# OttoPi10-RPi3A-HAT.net
KiCad netlist of a schematic drawn in EAGLE
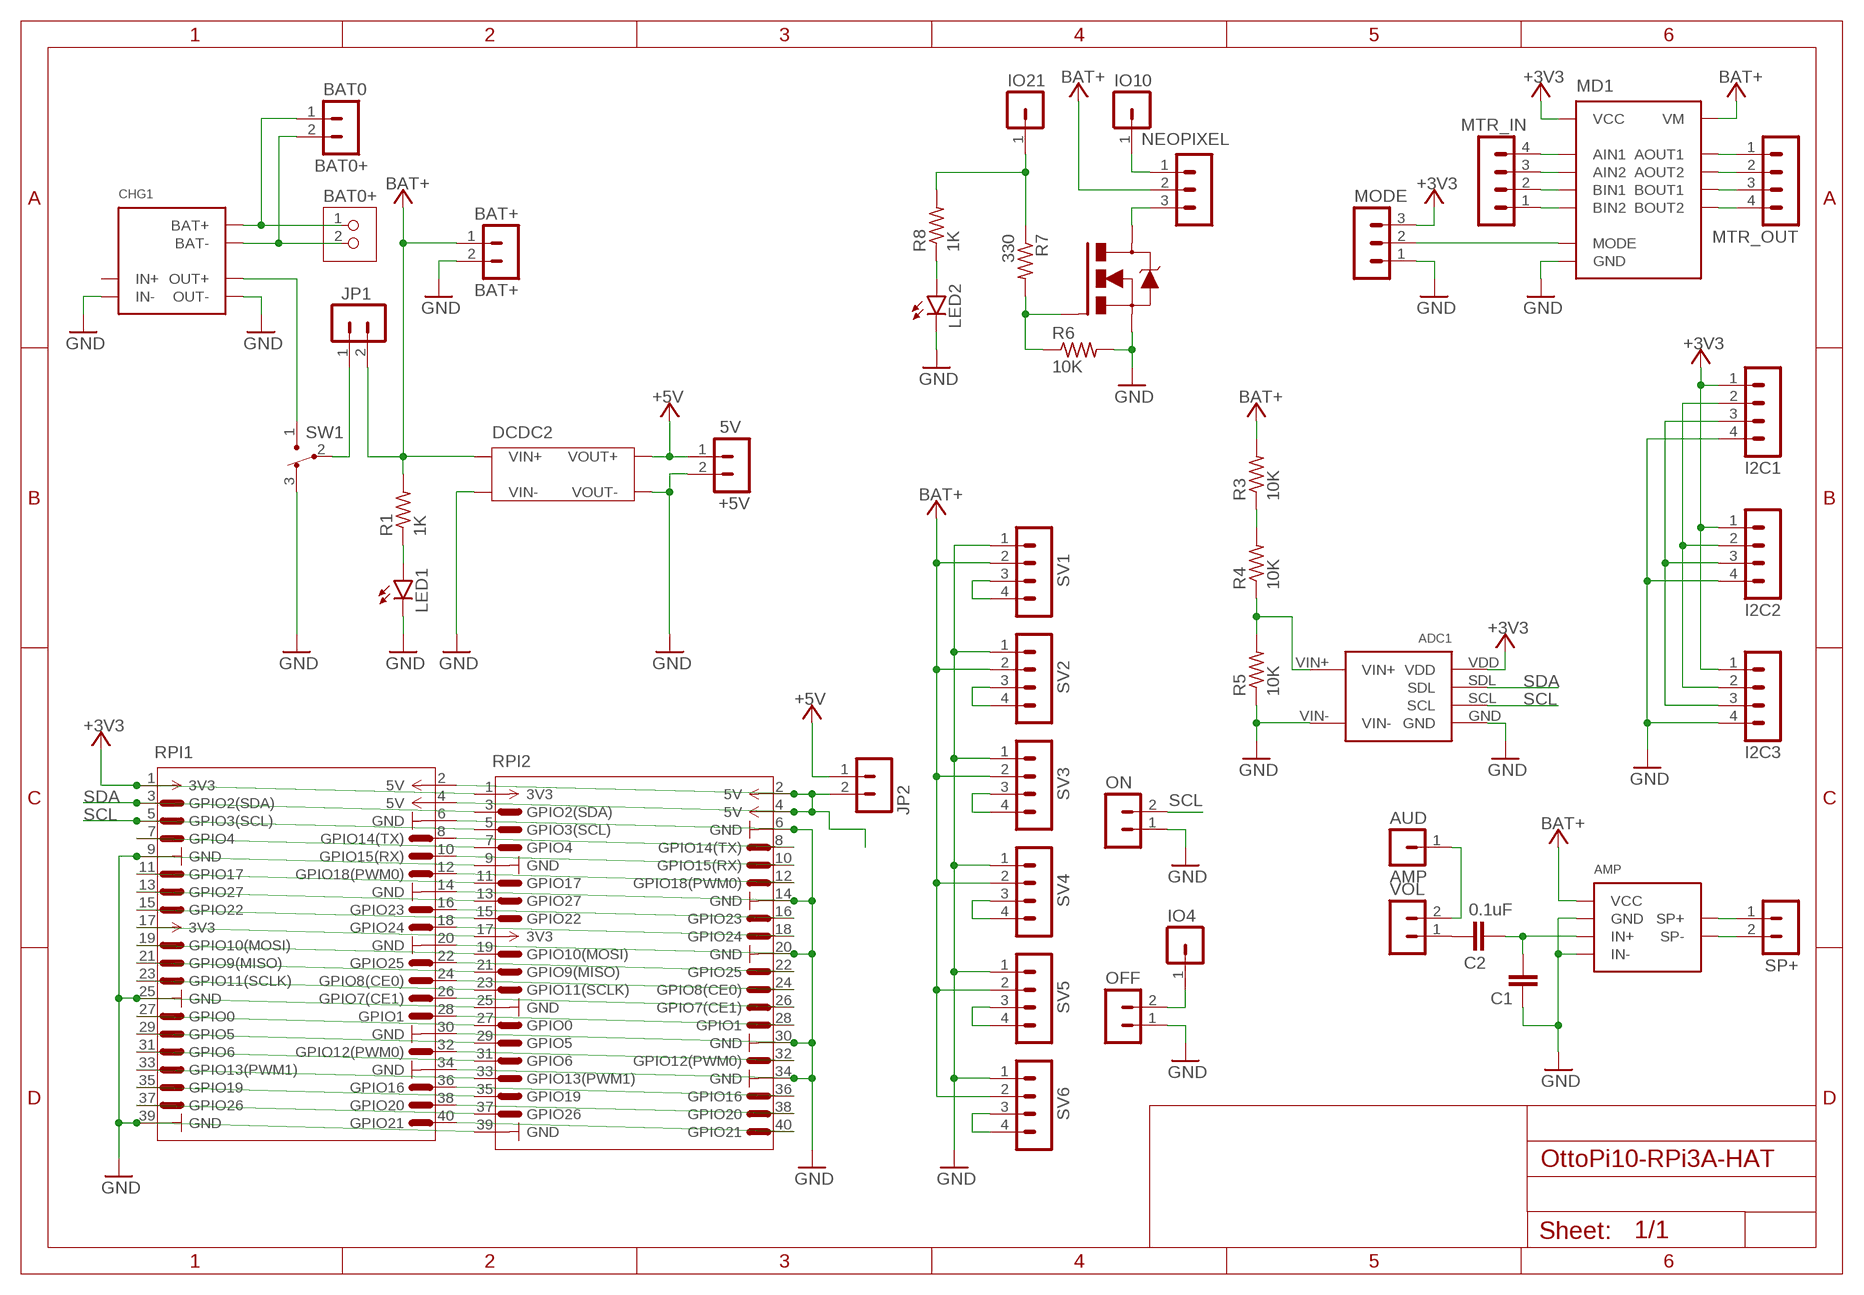
[diagram p0: schematic, sheet 1]

(export (version "E")
  (design (tool "Eeschema 10.0.6"))
  (components
    (comp (ref "+5V")
      (value "5V")
      (footprint "eagle-import:PINHEAD-MA02-1")
      (libsource (lib "eagle-import") (part "PINHEAD-MA02-1"))
    )
    (comp (ref "ADC1")
      (value "MCP3425MOD")
      (footprint "eagle-import:MCP3425MOD")
      (libsource (lib "eagle-import") (part "MCP3425MOD"))
    )
    (comp (ref "AMP")
      (value "AMP")
      (footprint "eagle-import:PAM8012MOD-A")
      (libsource (lib "eagle-import") (part "PAM8012MOD"))
    )
    (comp (ref "AUD")
      (value "AMP")
      (footprint "eagle-import:PINHEAD-MA01-1")
      (libsource (lib "eagle-import") (part "PINHEAD-MA01-1"))
    )
    (comp (ref "BAT+")
      (value "BAT+")
      (footprint "eagle-import:PINHEAD-MA02-1")
      (libsource (lib "eagle-import") (part "PINHEAD-MA02-1"))
    )
    (comp (ref "BAT0")
      (value "BAT0+")
      (footprint "eagle-import:PINHEAD-MA02-1")
      (libsource (lib "eagle-import") (part "PINHEAD-MA02-1"))
    )
    (comp (ref "BAT0+")
      (value "JST-PH2")
      (footprint "eagle-import:JST-PH2")
      (libsource (lib "eagle-import") (part "JST-PH2"))
    )
    (comp (ref "C1")
      (value "C-EU025-024X044")
      (footprint "eagle-import:C025-024X044")
      (libsource (lib "eagle-import") (part "C-EU025-024X044"))
    )
    (comp (ref "C2")
      (value "0.1uF")
      (footprint "eagle-import:C025-024X044")
      (libsource (lib "eagle-import") (part "C-EU025-024X044"))
    )
    (comp (ref "CHG1")
      (value "TP4056MOD1")
      (footprint "eagle-import:TP4056MOD1")
      (libsource (lib "eagle-import") (part "TP4056MOD1"))
    )
    (comp (ref "DCDC2")
      (value "DCDC-SX1308-MOD1")
      (footprint "eagle-import:DCDC-SX1308-MOD1")
      (libsource (lib "eagle-import") (part "DCDC-SX1308-MOD1"))
    )
    (comp (ref "I2C1")
      (value "PINHEAD-MA04-1")
      (footprint "eagle-import:PINHEAD-MA04-1")
      (libsource (lib "eagle-import") (part "PINHEAD-MA04-1"))
    )
    (comp (ref "I2C2")
      (value "PINHEAD-MA04-1")
      (footprint "eagle-import:PINHEAD-MA04-1")
      (libsource (lib "eagle-import") (part "PINHEAD-MA04-1"))
    )
    (comp (ref "I2C3")
      (value "PINHEAD-MA04-1")
      (footprint "eagle-import:PINHEAD-MA04-1")
      (libsource (lib "eagle-import") (part "PINHEAD-MA04-1"))
    )
    (comp (ref "IO4")
      (value "PINHEAD-MA01-1")
      (footprint "eagle-import:PINHEAD-MA01-1")
      (libsource (lib "eagle-import") (part "PINHEAD-MA01-1"))
    )
    (comp (ref "IO10")
      (value "PINHEAD-MA01-1")
      (footprint "eagle-import:PINHEAD-MA01-1")
      (libsource (lib "eagle-import") (part "PINHEAD-MA01-1"))
    )
    (comp (ref "IO21")
      (value "PINHEAD-MA01-1")
      (footprint "eagle-import:PINHEAD-MA01-1")
      (libsource (lib "eagle-import") (part "PINHEAD-MA01-1"))
    )
    (comp (ref "JP1")
      (value "PINHEAD-MA02-1")
      (footprint "eagle-import:PINHEAD-MA02-1")
      (libsource (lib "eagle-import") (part "PINHEAD-MA02-1"))
    )
    (comp (ref "JP2")
      (value "PINHEAD-MA02-1")
      (footprint "eagle-import:PINHEAD-MA02-1")
      (libsource (lib "eagle-import") (part "PINHEAD-MA02-1"))
    )
    (comp (ref "LED1")
      (value "LED3MM")
      (footprint "eagle-import:LED3MM")
      (libsource (lib "eagle-import") (part "LED3MM"))
    )
    (comp (ref "LED2")
      (value "LED3MM")
      (footprint "eagle-import:LED3MM")
      (libsource (lib "eagle-import") (part "LED3MM"))
    )
    (comp (ref "MD1")
      (value "DRV8835MOD")
      (footprint "eagle-import:DRV8835MOD")
      (libsource (lib "eagle-import") (part "DRV8835MOD"))
    )
    (comp (ref "MODE")
      (value "PINHEAD-MA03-1")
      (footprint "eagle-import:PINHEAD-MA03-1")
      (libsource (lib "eagle-import") (part "PINHEAD-MA03-1"))
    )
    (comp (ref "MTR_IN")
      (value "PINHEAD-MA04-1")
      (footprint "eagle-import:PINHEAD-MA04-1")
      (libsource (lib "eagle-import") (part "PINHEAD-MA04-1"))
    )
    (comp (ref "MTR_OUT")
      (value "PINHEAD-MA04-1")
      (footprint "eagle-import:PINHEAD-MA04-1")
      (libsource (lib "eagle-import") (part "PINHEAD-MA04-1"))
    )
    (comp (ref "NEOPIXEL")
      (value "PINHEAD-MA03-1")
      (footprint "eagle-import:PINHEAD-MA03-1")
      (libsource (lib "eagle-import") (part "ytani1_30941153_PINHEAD-MA03-1"))
    )
    (comp (ref "OFF")
      (value "PINHEAD-MA02-1")
      (footprint "eagle-import:PINHEAD-MA02-1")
      (libsource (lib "eagle-import") (part "PINHEAD-MA02-1"))
    )
    (comp (ref "ON")
      (value "PINHEAD-MA02-1")
      (footprint "eagle-import:PINHEAD-MA02-1")
      (libsource (lib "eagle-import") (part "PINHEAD-MA02-1"))
    )
    (comp (ref "Q1")
      (value "2SK4017")
      (footprint "eagle-import:MOSFET-1")
      (libsource (lib "eagle-import") (part "MOSFET-2SK4017"))
    )
    (comp (ref "R1")
      (value "1K")
      (footprint "eagle-import:0204_7")
      (libsource (lib "eagle-import") (part "R-US_0204/7"))
    )
    (comp (ref "R3")
      (value "10K")
      (footprint "eagle-import:0204_7")
      (libsource (lib "eagle-import") (part "R-US_0204/7"))
    )
    (comp (ref "R4")
      (value "10K")
      (footprint "eagle-import:0204_7")
      (libsource (lib "eagle-import") (part "R-US_0204/7"))
    )
    (comp (ref "R5")
      (value "10K")
      (footprint "eagle-import:0204_7")
      (libsource (lib "eagle-import") (part "R-US_0204/7"))
    )
    (comp (ref "R6")
      (value "10K")
      (footprint "eagle-import:0204_7")
      (libsource (lib "eagle-import") (part "R-US_0204/7"))
    )
    (comp (ref "R7")
      (value "330")
      (footprint "eagle-import:0204_7")
      (libsource (lib "eagle-import") (part "R-US_0204/7"))
    )
    (comp (ref "R8")
      (value "1K")
      (footprint "eagle-import:0204_7")
      (libsource (lib "eagle-import") (part "R-US_0204/7"))
    )
    (comp (ref "RPI1")
      (value "RPI-PIN")
      (footprint "eagle-import:RPI-PIN")
      (libsource (lib "eagle-import") (part "RPI-PIN"))
    )
    (comp (ref "RPI2")
      (value "RPI-PIN")
      (footprint "eagle-import:RPI-PIN")
      (libsource (lib "eagle-import") (part "RPI-PIN"))
    )
    (comp (ref "SP+")
      (value "PINHEAD-MA02-1")
      (footprint "eagle-import:PINHEAD-MA02-1")
      (libsource (lib "eagle-import") (part "PINHEAD-MA02-1"))
    )
    (comp (ref "SV1")
      (value "PINHEAD-MA04-1")
      (footprint "eagle-import:PINHEAD-MA04-1")
      (libsource (lib "eagle-import") (part "PINHEAD-MA04-1"))
    )
    (comp (ref "SV2")
      (value "PINHEAD-MA04-1")
      (footprint "eagle-import:PINHEAD-MA04-1")
      (libsource (lib "eagle-import") (part "PINHEAD-MA04-1"))
    )
    (comp (ref "SV3")
      (value "PINHEAD-MA04-1")
      (footprint "eagle-import:PINHEAD-MA04-1")
      (libsource (lib "eagle-import") (part "PINHEAD-MA04-1"))
    )
    (comp (ref "SV4")
      (value "PINHEAD-MA04-1")
      (footprint "eagle-import:PINHEAD-MA04-1")
      (libsource (lib "eagle-import") (part "PINHEAD-MA04-1"))
    )
    (comp (ref "SV5")
      (value "PINHEAD-MA04-1")
      (footprint "eagle-import:PINHEAD-MA04-1")
      (libsource (lib "eagle-import") (part "PINHEAD-MA04-1"))
    )
    (comp (ref "SV6")
      (value "PINHEAD-MA04-1")
      (footprint "eagle-import:PINHEAD-MA04-1")
      (libsource (lib "eagle-import") (part "PINHEAD-MA04-1"))
    )
    (comp (ref "SW1")
      (value "SW3-1")
      (footprint "eagle-import:SW3-1")
      (fields (field (name "MF") "HiLetgo"))
      (libsource (lib "eagle-import") (part "SW3-1"))
    )
    (comp (ref "VOL")
      (value "PINHEAD-MA02-1")
      (footprint "eagle-import:PINHEAD-MA02-1")
      (libsource (lib "eagle-import") (part "PINHEAD-MA02-1"))
    )
  )
  (nets
    (net (code "1") (name "+3V3") (class "Default")
      (node (ref "ADC1") (pin "VDD") (pinfunction "VDD_VDD") (pintype "bidirectional"))
      (node (ref "I2C1") (pin "1") (pinfunction "1_1") (pintype "passive"))
      (node (ref "I2C2") (pin "1") (pinfunction "1_1") (pintype "passive"))
      (node (ref "I2C3") (pin "1") (pinfunction "1_1") (pintype "passive"))
      (node (ref "MD1") (pin "VCC") (pinfunction "VCC_VCC") (pintype "input"))
      (node (ref "MODE") (pin "3") (pinfunction "3_3") (pintype "passive"))
      (node (ref "RPI1") (pin "1") (pinfunction "3V3_1") (pintype "passive"))
      (node (ref "RPI2") (pin "1") (pinfunction "3V3_1") (pintype "passive"))
    )
    (net (code "2") (name "+5V") (class "Default")
      (node (ref "+5V") (pin "1") (pinfunction "1_1") (pintype "passive"))
      (node (ref "DCDC2") (pin "VOUT+") (pinfunction "VOUT+_VOUT+") (pintype "power_in"))
      (node (ref "JP2") (pin "1") (pinfunction "1_1") (pintype "passive"))
    )
    (net (code "3") (name "/SCL") (class "Default")
      (node (ref "ADC1") (pin "SCL") (pinfunction "SCL_SCL") (pintype "bidirectional"))
      (node (ref "I2C1") (pin "3") (pinfunction "3_3") (pintype "passive"))
      (node (ref "I2C2") (pin "3") (pinfunction "3_3") (pintype "passive"))
      (node (ref "I2C3") (pin "3") (pinfunction "3_3") (pintype "passive"))
      (node (ref "ON") (pin "2") (pinfunction "2_2") (pintype "passive"))
      (node (ref "RPI1") (pin "5") (pinfunction "GPIO3(SCL)_5") (pintype "passive"))
      (node (ref "RPI2") (pin "5") (pinfunction "GPIO3(SCL)_5") (pintype "passive"))
    )
    (net (code "4") (name "/SDA") (class "Default")
      (node (ref "ADC1") (pin "SDL") (pinfunction "SDL_SDL") (pintype "bidirectional"))
      (node (ref "I2C1") (pin "2") (pinfunction "2_2") (pintype "passive"))
      (node (ref "I2C2") (pin "2") (pinfunction "2_2") (pintype "passive"))
      (node (ref "I2C3") (pin "2") (pinfunction "2_2") (pintype "passive"))
      (node (ref "RPI1") (pin "3") (pinfunction "GPIO2(SDA)_3") (pintype "passive"))
      (node (ref "RPI2") (pin "3") (pinfunction "GPIO2(SDA)_3") (pintype "passive"))
    )
    (net (code "5") (name "BAT+") (class "Default")
      (node (ref "AMP") (pin "V+") (pinfunction "VCC_V+") (pintype "passive"))
      (node (ref "BAT+") (pin "1") (pinfunction "1_1") (pintype "passive"))
      (node (ref "DCDC2") (pin "VIN+") (pinfunction "VIN+_VIN+") (pintype "power_in"))
      (node (ref "JP1") (pin "2") (pinfunction "2_2") (pintype "passive"))
      (node (ref "MD1") (pin "VM") (pinfunction "VM_VM") (pintype "input"))
      (node (ref "NEOPIXEL") (pin "2") (pinfunction "2_2") (pintype "passive"))
      (node (ref "R1") (pin "2") (pinfunction "2_2") (pintype "passive"))
      (node (ref "R3") (pin "2") (pinfunction "2_2") (pintype "passive"))
      (node (ref "SV1") (pin "2") (pinfunction "2_2") (pintype "passive"))
      (node (ref "SV2") (pin "2") (pinfunction "2_2") (pintype "passive"))
      (node (ref "SV3") (pin "2") (pinfunction "2_2") (pintype "passive"))
      (node (ref "SV4") (pin "2") (pinfunction "2_2") (pintype "passive"))
      (node (ref "SV5") (pin "2") (pinfunction "2_2") (pintype "passive"))
      (node (ref "SV6") (pin "2") (pinfunction "2_2") (pintype "passive"))
    )
    (net (code "6") (name "GND") (class "Default")
      (node (ref "+5V") (pin "2") (pinfunction "2_2") (pintype "passive"))
      (node (ref "ADC1") (pin "GND") (pinfunction "GND_GND") (pintype "bidirectional"))
      (node (ref "ADC1") (pin "VIN-") (pinfunction "VIN-_VIN-") (pintype "bidirectional"))
      (node (ref "AMP") (pin "GND") (pinfunction "GND_GND") (pintype "passive"))
      (node (ref "AMP") (pin "IN-") (pinfunction "IN-_IN-") (pintype "input"))
      (node (ref "BAT+") (pin "2") (pinfunction "2_2") (pintype "passive"))
      (node (ref "C1") (pin "1") (pinfunction "1_1") (pintype "passive"))
      (node (ref "CHG1") (pin "IN-") (pinfunction "IN-_IN-") (pintype "passive"))
      (node (ref "CHG1") (pin "OUT-") (pinfunction "OUT-_OUT-") (pintype "passive"))
      (node (ref "DCDC2") (pin "VIN-") (pinfunction "VIN-_VIN-") (pintype "power_in"))
      (node (ref "DCDC2") (pin "VOUT-") (pinfunction "VOUT-_VOUT-") (pintype "power_in"))
      (node (ref "I2C1") (pin "4") (pinfunction "4_4") (pintype "passive"))
      (node (ref "I2C2") (pin "4") (pinfunction "4_4") (pintype "passive"))
      (node (ref "I2C3") (pin "4") (pinfunction "4_4") (pintype "passive"))
      (node (ref "LED1") (pin "K") (pinfunction "C_K") (pintype "passive"))
      (node (ref "LED2") (pin "K") (pinfunction "C_K") (pintype "passive"))
      (node (ref "MD1") (pin "GND") (pinfunction "GND_GND") (pintype "power_in"))
      (node (ref "MODE") (pin "1") (pinfunction "1_1") (pintype "passive"))
      (node (ref "OFF") (pin "1") (pinfunction "1_1") (pintype "passive"))
      (node (ref "ON") (pin "1") (pinfunction "1_1") (pintype "passive"))
      (node (ref "Q1") (pin "S") (pinfunction "S_S") (pintype "bidirectional"))
      (node (ref "R5") (pin "1") (pinfunction "1_1") (pintype "passive"))
      (node (ref "R6") (pin "2") (pinfunction "2_2") (pintype "passive"))
      (node (ref "RPI1") (pin "14") (pinfunction "GND_14") (pintype "passive"))
      (node (ref "RPI1") (pin "20") (pinfunction "GND_20") (pintype "passive"))
      (node (ref "RPI1") (pin "25") (pinfunction "GND_25") (pintype "passive"))
      (node (ref "RPI1") (pin "30") (pinfunction "GND_30") (pintype "passive"))
      (node (ref "RPI1") (pin "34") (pinfunction "GND_34") (pintype "passive"))
      (node (ref "RPI1") (pin "39") (pinfunction "GND_39") (pintype "passive"))
      (node (ref "RPI1") (pin "6") (pinfunction "GND_6") (pintype "passive"))
      (node (ref "RPI1") (pin "9") (pinfunction "GND_9") (pintype "passive"))
      (node (ref "RPI2") (pin "14") (pinfunction "GND_14") (pintype "passive"))
      (node (ref "RPI2") (pin "20") (pinfunction "GND_20") (pintype "passive"))
      (node (ref "RPI2") (pin "25") (pinfunction "GND_25") (pintype "passive"))
      (node (ref "RPI2") (pin "30") (pinfunction "GND_30") (pintype "passive"))
      (node (ref "RPI2") (pin "34") (pinfunction "GND_34") (pintype "passive"))
      (node (ref "RPI2") (pin "39") (pinfunction "GND_39") (pintype "passive"))
      (node (ref "RPI2") (pin "6") (pinfunction "GND_6") (pintype "passive"))
      (node (ref "RPI2") (pin "9") (pinfunction "GND_9") (pintype "passive"))
      (node (ref "SV1") (pin "1") (pinfunction "1_1") (pintype "passive"))
      (node (ref "SV2") (pin "1") (pinfunction "1_1") (pintype "passive"))
      (node (ref "SV3") (pin "1") (pinfunction "1_1") (pintype "passive"))
      (node (ref "SV4") (pin "1") (pinfunction "1_1") (pintype "passive"))
      (node (ref "SV5") (pin "1") (pinfunction "1_1") (pintype "passive"))
      (node (ref "SV6") (pin "1") (pinfunction "1_1") (pintype "passive"))
      (node (ref "SW1") (pin "3") (pinfunction "3_3") (pintype "passive"))
    )
    (net (code "7") (name "Net-(ADC1-PadVIN+)") (class "Default")
      (node (ref "ADC1") (pin "VIN+") (pinfunction "VIN+_VIN+") (pintype "bidirectional"))
      (node (ref "R4") (pin "1") (pinfunction "1_1") (pintype "passive"))
      (node (ref "R5") (pin "2") (pinfunction "2_2") (pintype "passive"))
    )
    (net (code "8") (name "Net-(AMP-PadIN+)") (class "Default")
      (node (ref "AMP") (pin "IN+") (pinfunction "IN+_IN+") (pintype "input"))
      (node (ref "C1") (pin "2") (pinfunction "2_2") (pintype "passive"))
      (node (ref "C2") (pin "1") (pinfunction "1_1") (pintype "passive"))
    )
    (net (code "9") (name "Net-(AMP-SP+)") (class "Default")
      (node (ref "AMP") (pin "SP+@1") (pinfunction "SP+_SP+@1") (pintype "output"))
      (node (ref "SP+") (pin "1") (pinfunction "1_1") (pintype "passive"))
    )
    (net (code "10") (name "Net-(AMP-SP-)") (class "Default")
      (node (ref "AMP") (pin "SP-@1") (pinfunction "SP-_SP-@1") (pintype "output"))
      (node (ref "SP+") (pin "2") (pinfunction "2_2") (pintype "passive"))
    )
    (net (code "11") (name "Net-(AUD-Pad1)") (class "Default")
      (node (ref "AUD") (pin "1") (pinfunction "1_1") (pintype "passive"))
      (node (ref "VOL") (pin "2") (pinfunction "2_2") (pintype "passive"))
    )
    (net (code "12") (name "Net-(BAT0+-Pad1)") (class "Default")
      (node (ref "BAT0") (pin "1") (pinfunction "1_1") (pintype "passive"))
      (node (ref "BAT0+") (pin "1") (pinfunction "1_1") (pintype "passive"))
      (node (ref "CHG1") (pin "BAT+") (pinfunction "BAT+_BAT+") (pintype "passive"))
    )
    (net (code "13") (name "Net-(BAT0+-Pad2)") (class "Default")
      (node (ref "BAT0") (pin "2") (pinfunction "2_2") (pintype "passive"))
      (node (ref "BAT0+") (pin "2") (pinfunction "2_2") (pintype "passive"))
      (node (ref "CHG1") (pin "BAT-") (pinfunction "BAT-_BAT-") (pintype "passive"))
    )
    (net (code "14") (name "Net-(C2-Pad2)") (class "Default")
      (node (ref "C2") (pin "2") (pinfunction "2_2") (pintype "passive"))
      (node (ref "VOL") (pin "1") (pinfunction "1_1") (pintype "passive"))
    )
    (net (code "15") (name "Net-(CHG1-PadOUT+)") (class "Default")
      (node (ref "CHG1") (pin "OUT+") (pinfunction "OUT+_OUT+") (pintype "passive"))
      (node (ref "SW1") (pin "1") (pinfunction "1_1") (pintype "passive"))
    )
    (net (code "16") (name "Net-(IO4-Pad1)") (class "Default")
      (node (ref "IO4") (pin "1") (pinfunction "1_1") (pintype "passive"))
      (node (ref "OFF") (pin "2") (pinfunction "2_2") (pintype "passive"))
    )
    (net (code "17") (name "Net-(IO10-Pad1)") (class "Default")
      (node (ref "IO10") (pin "1") (pinfunction "1_1") (pintype "passive"))
      (node (ref "NEOPIXEL") (pin "1") (pinfunction "1_1") (pintype "passive"))
    )
    (net (code "18") (name "Net-(IO21-Pad1)") (class "Default")
      (node (ref "IO21") (pin "1") (pinfunction "1_1") (pintype "passive"))
      (node (ref "R7") (pin "1") (pinfunction "1_1") (pintype "passive"))
      (node (ref "R8") (pin "2") (pinfunction "2_2") (pintype "passive"))
    )
    (net (code "19") (name "Net-(JP1-Pad1)") (class "Default")
      (node (ref "JP1") (pin "1") (pinfunction "1_1") (pintype "passive"))
      (node (ref "SW1") (pin "2") (pinfunction "2_2") (pintype "passive"))
    )
    (net (code "20") (name "Net-(JP2-Pad2)") (class "Default")
      (node (ref "JP2") (pin "2") (pinfunction "2_2") (pintype "passive"))
      (node (ref "RPI1") (pin "2") (pinfunction "5V_2") (pintype "passive"))
      (node (ref "RPI1") (pin "4") (pinfunction "5V_4") (pintype "passive"))
      (node (ref "RPI2") (pin "2") (pinfunction "5V_2") (pintype "passive"))
      (node (ref "RPI2") (pin "4") (pinfunction "5V_4") (pintype "passive"))
    )
    (net (code "21") (name "Net-(LED1-PadA)") (class "Default")
      (node (ref "LED1") (pin "A") (pinfunction "A_A") (pintype "passive"))
      (node (ref "R1") (pin "1") (pinfunction "1_1") (pintype "passive"))
    )
    (net (code "22") (name "Net-(LED2-PadA)") (class "Default")
      (node (ref "LED2") (pin "A") (pinfunction "A_A") (pintype "passive"))
      (node (ref "R8") (pin "1") (pinfunction "1_1") (pintype "passive"))
    )
    (net (code "23") (name "Net-(MD1-PadAIN1)") (class "Default")
      (node (ref "MD1") (pin "AIN1") (pinfunction "AIN1_AIN1") (pintype "input"))
      (node (ref "MTR_IN") (pin "4") (pinfunction "4_4") (pintype "passive"))
    )
    (net (code "24") (name "Net-(MD1-PadAIN2)") (class "Default")
      (node (ref "MD1") (pin "AIN2") (pinfunction "AIN2_AIN2") (pintype "input"))
      (node (ref "MTR_IN") (pin "3") (pinfunction "3_3") (pintype "passive"))
    )
    (net (code "25") (name "Net-(MD1-PadAOUT1)") (class "Default")
      (node (ref "MD1") (pin "AOUT1") (pinfunction "AOUT1_AOUT1") (pintype "output"))
      (node (ref "MTR_OUT") (pin "1") (pinfunction "1_1") (pintype "passive"))
    )
    (net (code "26") (name "Net-(MD1-PadAOUT2)") (class "Default")
      (node (ref "MD1") (pin "AOUT2") (pinfunction "AOUT2_AOUT2") (pintype "output"))
      (node (ref "MTR_OUT") (pin "2") (pinfunction "2_2") (pintype "passive"))
    )
    (net (code "27") (name "Net-(MD1-PadBIN1)") (class "Default")
      (node (ref "MD1") (pin "BIN1") (pinfunction "BIN1_BIN1") (pintype "input"))
      (node (ref "MTR_IN") (pin "2") (pinfunction "2_2") (pintype "passive"))
    )
    (net (code "28") (name "Net-(MD1-PadBIN2)") (class "Default")
      (node (ref "MD1") (pin "BIN2") (pinfunction "BIN2_BIN2") (pintype "input"))
      (node (ref "MTR_IN") (pin "1") (pinfunction "1_1") (pintype "passive"))
    )
    (net (code "29") (name "Net-(MD1-PadBOUT1)") (class "Default")
      (node (ref "MD1") (pin "BOUT1") (pinfunction "BOUT1_BOUT1") (pintype "output"))
      (node (ref "MTR_OUT") (pin "3") (pinfunction "3_3") (pintype "passive"))
    )
    (net (code "30") (name "Net-(MD1-PadBOUT2)") (class "Default")
      (node (ref "MD1") (pin "BOUT2") (pinfunction "BOUT2_BOUT2") (pintype "output"))
      (node (ref "MTR_OUT") (pin "4") (pinfunction "4_4") (pintype "passive"))
    )
    (net (code "31") (name "Net-(MD1-PadMODE)") (class "Default")
      (node (ref "MD1") (pin "MODE") (pinfunction "MODE_MODE") (pintype "input"))
      (node (ref "MODE") (pin "2") (pinfunction "2_2") (pintype "passive"))
    )
    (net (code "32") (name "Net-(NEOPIXEL-Pad3)") (class "Default")
      (node (ref "NEOPIXEL") (pin "3") (pinfunction "3_3") (pintype "passive"))
      (node (ref "Q1") (pin "D") (pinfunction "D_D") (pintype "bidirectional"))
    )
    (net (code "33") (name "Net-(Q1-PadG)") (class "Default")
      (node (ref "Q1") (pin "G") (pinfunction "G_G") (pintype "bidirectional"))
      (node (ref "R6") (pin "1") (pinfunction "1_1") (pintype "passive"))
      (node (ref "R7") (pin "2") (pinfunction "2_2") (pintype "passive"))
    )
    (net (code "34") (name "Net-(R3-Pad1)") (class "Default")
      (node (ref "R3") (pin "1") (pinfunction "1_1") (pintype "passive"))
      (node (ref "R4") (pin "2") (pinfunction "2_2") (pintype "passive"))
    )
    (net (code "35") (name "Net-(RPI1-3V3-Pad17)") (class "Default")
      (node (ref "RPI1") (pin "17") (pinfunction "3V3_17") (pintype "passive"))
      (node (ref "RPI2") (pin "17") (pinfunction "3V3_17") (pintype "passive"))
    )
    (net (code "36") (name "Net-(RPI1-GPIO0)") (class "Default")
      (node (ref "RPI1") (pin "27") (pinfunction "GPIO0_27") (pintype "passive"))
      (node (ref "RPI2") (pin "27") (pinfunction "GPIO0_27") (pintype "passive"))
    )
    (net (code "37") (name "Net-(RPI1-GPIO1)") (class "Default")
      (node (ref "RPI1") (pin "28") (pinfunction "GPIO1_28") (pintype "passive"))
      (node (ref "RPI2") (pin "28") (pinfunction "GPIO1_28") (pintype "passive"))
    )
    (net (code "38") (name "Net-(RPI1-GPIO4)") (class "Default")
      (node (ref "RPI1") (pin "7") (pinfunction "GPIO4_7") (pintype "passive"))
      (node (ref "RPI2") (pin "7") (pinfunction "GPIO4_7") (pintype "passive"))
    )
    (net (code "39") (name "Net-(RPI1-GPIO5)") (class "Default")
      (node (ref "RPI1") (pin "29") (pinfunction "GPIO5_29") (pintype "passive"))
      (node (ref "RPI2") (pin "29") (pinfunction "GPIO5_29") (pintype "passive"))
    )
    (net (code "40") (name "Net-(RPI1-GPIO6)") (class "Default")
      (node (ref "RPI1") (pin "31") (pinfunction "GPIO6_31") (pintype "passive"))
      (node (ref "RPI2") (pin "31") (pinfunction "GPIO6_31") (pintype "passive"))
    )
    (net (code "41") (name "Net-(RPI1-GPIO7(CE1))") (class "Default")
      (node (ref "RPI1") (pin "26") (pinfunction "GPIO7(CE1)_26") (pintype "passive"))
      (node (ref "RPI2") (pin "26") (pinfunction "GPIO7(CE1)_26") (pintype "passive"))
    )
    (net (code "42") (name "Net-(RPI1-GPIO8(CE0))") (class "Default")
      (node (ref "RPI1") (pin "24") (pinfunction "GPIO8(CE0)_24") (pintype "passive"))
      (node (ref "RPI2") (pin "24") (pinfunction "GPIO8(CE0)_24") (pintype "passive"))
    )
    (net (code "43") (name "Net-(RPI1-GPIO9(MISO))") (class "Default")
      (node (ref "RPI1") (pin "21") (pinfunction "GPIO9(MISO)_21") (pintype "passive"))
      (node (ref "RPI2") (pin "21") (pinfunction "GPIO9(MISO)_21") (pintype "passive"))
    )
    (net (code "44") (name "Net-(RPI1-GPIO10(MOSI))") (class "Default")
      (node (ref "RPI1") (pin "19") (pinfunction "GPIO10(MOSI)_19") (pintype "passive"))
      (node (ref "RPI2") (pin "19") (pinfunction "GPIO10(MOSI)_19") (pintype "passive"))
    )
    (net (code "45") (name "Net-(RPI1-GPIO11(SCLK))") (class "Default")
      (node (ref "RPI1") (pin "23") (pinfunction "GPIO11(SCLK)_23") (pintype "passive"))
      (node (ref "RPI2") (pin "23") (pinfunction "GPIO11(SCLK)_23") (pintype "passive"))
    )
    (net (code "46") (name "Net-(RPI1-GPIO12(PWM0))") (class "Default")
      (node (ref "RPI1") (pin "32") (pinfunction "GPIO12(PWM0)_32") (pintype "passive"))
      (node (ref "RPI2") (pin "32") (pinfunction "GPIO12(PWM0)_32") (pintype "passive"))
    )
    (net (code "47") (name "Net-(RPI1-GPIO13(PWM1))") (class "Default")
      (node (ref "RPI1") (pin "33") (pinfunction "GPIO13(PWM1)_33") (pintype "passive"))
      (node (ref "RPI2") (pin "33") (pinfunction "GPIO13(PWM1)_33") (pintype "passive"))
    )
    (net (code "48") (name "Net-(RPI1-GPIO14(TX))") (class "Default")
      (node (ref "RPI1") (pin "8") (pinfunction "GPIO14(TX)_8") (pintype "passive"))
      (node (ref "RPI2") (pin "8") (pinfunction "GPIO14(TX)_8") (pintype "passive"))
    )
    (net (code "49") (name "Net-(RPI1-GPIO15(RX))") (class "Default")
      (node (ref "RPI1") (pin "10") (pinfunction "GPIO15(RX)_10") (pintype "passive"))
      (node (ref "RPI2") (pin "10") (pinfunction "GPIO15(RX)_10") (pintype "passive"))
    )
    (net (code "50") (name "Net-(RPI1-GPIO16)") (class "Default")
      (node (ref "RPI1") (pin "36") (pinfunction "GPIO16_36") (pintype "passive"))
      (node (ref "RPI2") (pin "36") (pinfunction "GPIO16_36") (pintype "passive"))
    )
    (net (code "51") (name "Net-(RPI1-GPIO17)") (class "Default")
      (node (ref "RPI1") (pin "11") (pinfunction "GPIO17_11") (pintype "passive"))
      (node (ref "RPI2") (pin "11") (pinfunction "GPIO17_11") (pintype "passive"))
    )
    (net (code "52") (name "Net-(RPI1-GPIO18(PWM0))") (class "Default")
      (node (ref "RPI1") (pin "12") (pinfunction "GPIO18(PWM0)_12") (pintype "passive"))
      (node (ref "RPI2") (pin "12") (pinfunction "GPIO18(PWM0)_12") (pintype "passive"))
    )
    (net (code "53") (name "Net-(RPI1-GPIO19)") (class "Default")
      (node (ref "RPI1") (pin "35") (pinfunction "GPIO19_35") (pintype "passive"))
      (node (ref "RPI2") (pin "35") (pinfunction "GPIO19_35") (pintype "passive"))
    )
    (net (code "54") (name "Net-(RPI1-GPIO20)") (class "Default")
      (node (ref "RPI1") (pin "38") (pinfunction "GPIO20_38") (pintype "passive"))
      (node (ref "RPI2") (pin "38") (pinfunction "GPIO20_38") (pintype "passive"))
    )
    (net (code "55") (name "Net-(RPI1-GPIO21)") (class "Default")
      (node (ref "RPI1") (pin "40") (pinfunction "GPIO21_40") (pintype "passive"))
      (node (ref "RPI2") (pin "40") (pinfunction "GPIO21_40") (pintype "passive"))
    )
    (net (code "56") (name "Net-(RPI1-GPIO22)") (class "Default")
      (node (ref "RPI1") (pin "15") (pinfunction "GPIO22_15") (pintype "passive"))
      (node (ref "RPI2") (pin "15") (pinfunction "GPIO22_15") (pintype "passive"))
    )
    (net (code "57") (name "Net-(RPI1-GPIO23)") (class "Default")
      (node (ref "RPI1") (pin "16") (pinfunction "GPIO23_16") (pintype "passive"))
      (node (ref "RPI2") (pin "16") (pinfunction "GPIO23_16") (pintype "passive"))
    )
    (net (code "58") (name "Net-(RPI1-GPIO24)") (class "Default")
      (node (ref "RPI1") (pin "18") (pinfunction "GPIO24_18") (pintype "passive"))
      (node (ref "RPI2") (pin "18") (pinfunction "GPIO24_18") (pintype "passive"))
    )
    (net (code "59") (name "Net-(RPI1-GPIO25)") (class "Default")
      (node (ref "RPI1") (pin "22") (pinfunction "GPIO25_22") (pintype "passive"))
      (node (ref "RPI2") (pin "22") (pinfunction "GPIO25_22") (pintype "passive"))
    )
    (net (code "60") (name "Net-(RPI1-GPIO26)") (class "Default")
      (node (ref "RPI1") (pin "37") (pinfunction "GPIO26_37") (pintype "passive"))
      (node (ref "RPI2") (pin "37") (pinfunction "GPIO26_37") (pintype "passive"))
    )
    (net (code "61") (name "Net-(RPI1-GPIO27)") (class "Default")
      (node (ref "RPI1") (pin "13") (pinfunction "GPIO27_13") (pintype "passive"))
      (node (ref "RPI2") (pin "13") (pinfunction "GPIO27_13") (pintype "passive"))
    )
    (net (code "62") (name "Net-(SV1-Pad3)") (class "Default")
      (node (ref "SV1") (pin "3") (pinfunction "3_3") (pintype "passive"))
      (node (ref "SV1") (pin "4") (pinfunction "4_4") (pintype "passive"))
    )
    (net (code "63") (name "Net-(SV2-Pad3)") (class "Default")
      (node (ref "SV2") (pin "3") (pinfunction "3_3") (pintype "passive"))
      (node (ref "SV2") (pin "4") (pinfunction "4_4") (pintype "passive"))
    )
    (net (code "64") (name "Net-(SV3-Pad3)") (class "Default")
      (node (ref "SV3") (pin "3") (pinfunction "3_3") (pintype "passive"))
      (node (ref "SV3") (pin "4") (pinfunction "4_4") (pintype "passive"))
    )
    (net (code "65") (name "Net-(SV4-Pad3)") (class "Default")
      (node (ref "SV4") (pin "3") (pinfunction "3_3") (pintype "passive"))
      (node (ref "SV4") (pin "4") (pinfunction "4_4") (pintype "passive"))
    )
    (net (code "66") (name "Net-(SV5-Pad3)") (class "Default")
      (node (ref "SV5") (pin "3") (pinfunction "3_3") (pintype "passive"))
      (node (ref "SV5") (pin "4") (pinfunction "4_4") (pintype "passive"))
    )
    (net (code "67") (name "Net-(SV6-Pad3)") (class "Default")
      (node (ref "SV6") (pin "3") (pinfunction "3_3") (pintype "passive"))
      (node (ref "SV6") (pin "4") (pinfunction "4_4") (pintype "passive"))
    )
    (net (code "68") (name "unconnected-(CHG1-PadIN+)") (class "Default")
      (node (ref "CHG1") (pin "IN+") (pinfunction "IN+_IN+") (pintype "passive"))
    )
  )
)
